# Sheet2.net
KiCad netlist of a schematic drawn in Altium Designer
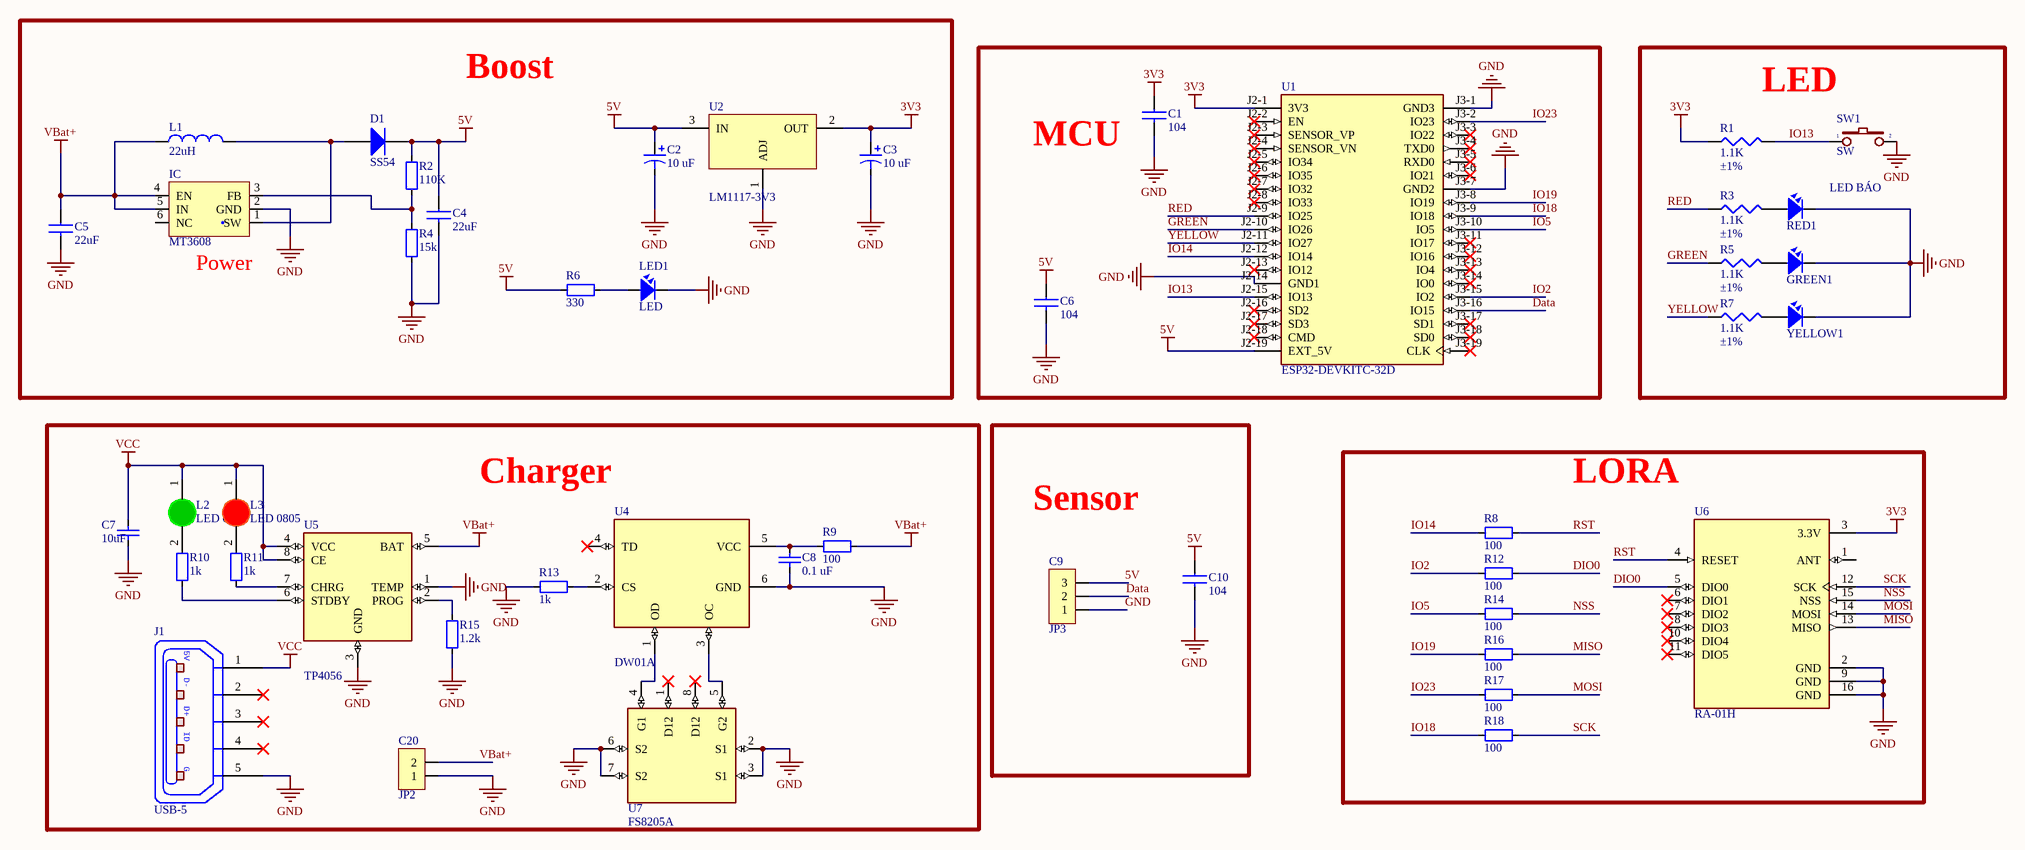
[diagram p0: Sheet2.SchDoc]

(export (version "E")
  (design (tool "Eeschema 10.0.6"))
  (components
    (comp (ref "C1")
      (value "104")
      (footprint "CAP0603")
      (description "CAP CER 30PF 50V NPO 0603")
      (fields
        (field (name "MANUFACTURER") "Yageo")
        (field (name "MANUFACTURER PART NUMBER") "CC0603JRNPO9BN300")
      )
      (libsource (lib "KhanhBK_SCH_Lib_6") (part "CC0603JRNPO9BN300"))
    )
    (comp (ref "C2")
      (value "10 uF")
      (footprint "C3MM")
      (description "Polarized Capacitor (Axial)")
      (fields (field (name "PUBLISHER") "Altium Limited"))
      (libsource (lib "My Library") (part "Cap Pol"))
    )
    (comp (ref "C3")
      (value "10 uF")
      (footprint "C3MM")
      (description "Polarized Capacitor (Axial)")
      (fields (field (name "PUBLISHER") "Altium Limited"))
      (libsource (lib "My Library") (part "Cap Pol"))
    )
    (comp (ref "C4")
      (value "22uF")
      (footprint "CAP0603")
      (description "CAP CER 30PF 50V NPO 0603")
      (fields
        (field (name "MANUFACTURER") "Yageo")
        (field (name "MANUFACTURER PART NUMBER") "CC0603JRNPO9BN300")
      )
      (libsource (lib "KhanhBK_SCH_Lib_6") (part "CC0603JRNPO9BN300"))
    )
    (comp (ref "C5")
      (value "22uF")
      (footprint "CAP0603")
      (description "CAP CER 30PF 50V NPO 0603")
      (fields
        (field (name "MANUFACTURER") "Yageo")
        (field (name "MANUFACTURER PART NUMBER") "CC0603JRNPO9BN300")
      )
      (libsource (lib "KhanhBK_SCH_Lib_6") (part "CC0603JRNPO9BN300"))
    )
    (comp (ref "C6")
      (value "104")
      (footprint "CAP0603")
      (description "CAP CER 30PF 50V NPO 0603")
      (fields
        (field (name "MANUFACTURER") "Yageo")
        (field (name "MANUFACTURER PART NUMBER") "CC0603JRNPO9BN300")
      )
      (libsource (lib "KhanhBK_SCH_Lib_6") (part "CC0603JRNPO9BN300"))
    )
    (comp (ref "C7")
      (value "10uF")
      (footprint "CAP_0805")
      (description "Capacitor")
      (fields (field (name "PUBLISHER") "Altium Limited"))
      (libsource (lib "My Library") (part "CapSMD"))
    )
    (comp (ref "C8")
      (value "0.1 uF")
      (footprint "CAP_0805")
      (description "Capacitor")
      (fields (field (name "PUBLISHER") "Altium Limited"))
      (libsource (lib "My Library") (part "CapSMD"))
    )
    (comp (ref "C9")
      (value "JP3")
      (footprint "JP3-C1T")
      (description "WR-PHD 2.54 mm Angled Socket Header")
      (fields
        (field (name "MANUFACTURER") "Würth Elektronik eiSos GmbH")
        (field (name "PARTNO") "613003143121")
        (field (name "CREATED BY") "Karrer Zheng")
      )
      (libsource (lib "KhanhBK_SCH_Library_1") (part "JP3"))
    )
    (comp (ref "C10")
      (value "104")
      (footprint "CAP0603")
      (description "CAP CER 30PF 50V NPO 0603")
      (fields
        (field (name "MANUFACTURER") "Yageo")
        (field (name "MANUFACTURER PART NUMBER") "CC0603JRNPO9BN300")
      )
      (libsource (lib "KhanhBK_SCH_Lib_6") (part "CC0603JRNPO9BN300"))
    )
    (comp (ref "C20")
      (value "JP2")
      (footprint "JP2-C1T")
      (description "WR-PHD 2.54 mm Angled Socket Header")
      (fields
        (field (name "MANUFACTURER") "Würth Elektronik eiSos GmbH")
        (field (name "PARTNO") "613002143121")
        (field (name "CREATED BY") "Karrer Zheng")
      )
      (libsource (lib "KhanhBK_SCH_Library_1") (part "JP2"))
    )
    (comp (ref "D1")
      (value "SS54")
      (footprint "DIODE/POW/1A")
      (description "Diode Power")
      (fields (field (name "PUBLISHER") "Altium Limited"))
      (libsource (lib "Cty1") (part "Diode Power"))
    )
    (comp (ref "GREEN1")
      (value "LED")
      (footprint "LED-3MM-GREEN")
      (description "LED Single colour Green and Red")
      (libsource (lib "KhanhBK_SCH_Library_1") (part "LED"))
    )
    (comp (ref "IC") (value "MT3608") (footprint "TSOP 2") (libsource (lib "MT3608") (part "MT3608")))
    (comp (ref "J1")
      (value "USB-5")
      (footprint "USB-M1")
      (fields
        (field (name "MANUFACTURER") "FCI")
        (field (name "MANUFACTURER PART NUMBER") "10118193-0001LF")
        (field (name ".CREATOR") "MM")
        (field (name ".CHECKED PCB") "RF")
        (field (name ".CHECKED SCH") "MM")
      )
      (libsource (lib "My Library") (part "USB-5"))
    )
    (comp (ref "L1")
      (value "22uH")
      (footprint "IND_400_500_212x114_SMD")
      (description "1mH Shielded Wirewound Inductor 600mA 1.82Ohm Max Nonstandard")
      (fields (field (name "MANUFACTURER") "Coilcraft") (field (name "MANUFACTURER PART NUMBER") "74477030"))
      (libsource (lib "Altium_Lib_by_KhueNguyenCreator") (part "IND_1mH-0.6A-20%-SMD"))
    )
    (comp (ref "L2")
      (value "LED 0805")
      (footprint "LED-0805-Green")
      (description "Dán")
      (libsource (lib "Altium_Lib_by_KhueNguyenCreator") (part "LED 0805 Xanh La"))
    )
    (comp (ref "L3")
      (value "LED 0805")
      (footprint "LED-0805-Red")
      (description "Dán")
      (libsource (lib "Altium_Lib_by_KhueNguyenCreator") (part "LED 0805 Do"))
    )
    (comp (ref "LED1")
      (value "LED")
      (footprint "LED-0805-Red")
      (description "LED Single colour Green and Red")
      (libsource (lib "My Library") (part "LED"))
    )
    (comp (ref "R1")
      (value "1.1K")
      (footprint "RES0603")
      (description "RES SMD 1K OHM 1% 1/10W 0603")
      (fields
        (field (name "MANUFACTURER") "Yageo")
        (field (name "MANUFACTURER PART NUMBER") "RT0603FRD071KL")
        (field (name "TOLERANCE") "±1%")
      )
      (libsource (lib "KhanhBK_SCH_Lib_6") (part "RT0603FRD071KL"))
    )
    (comp (ref "R2")
      (value "110K")
      (footprint "RES-SMD-0805")
      (description "Resistor")
      (fields
        (field (name "MANUFACTURER") "Generic Components")
        (field (name "PUBLISHER") "Altium Hobart Technology Centre")
      )
      (libsource (lib "My Library") (part "Resistor - SMD"))
    )
    (comp (ref "R3")
      (value "1.1K")
      (footprint "RES0603")
      (description "RES SMD 1K OHM 1% 1/10W 0603")
      (fields
        (field (name "MANUFACTURER") "Yageo")
        (field (name "MANUFACTURER PART NUMBER") "RT0603FRD071KL")
        (field (name "TOLERANCE") "±1%")
      )
      (libsource (lib "KhanhBK_SCH_Lib_6") (part "RT0603FRD071KL"))
    )
    (comp (ref "R4")
      (value "15k")
      (footprint "RES-SMD-0805")
      (description "Resistor")
      (fields
        (field (name "MANUFACTURER") "Generic Components")
        (field (name "PUBLISHER") "Altium Hobart Technology Centre")
      )
      (libsource (lib "My Library") (part "Resistor - SMD"))
    )
    (comp (ref "R5")
      (value "1.1K")
      (footprint "RES0603")
      (description "RES SMD 1K OHM 1% 1/10W 0603")
      (fields
        (field (name "MANUFACTURER") "Yageo")
        (field (name "MANUFACTURER PART NUMBER") "RT0603FRD071KL")
        (field (name "TOLERANCE") "±1%")
      )
      (libsource (lib "KhanhBK_SCH_Lib_6") (part "RT0603FRD071KL"))
    )
    (comp (ref "R6")
      (value "330")
      (footprint "RES-SMD-0805")
      (description "Resistor")
      (fields
        (field (name "MANUFACTURER") "Generic Components")
        (field (name "PUBLISHER") "Altium Hobart Technology Centre")
      )
      (libsource (lib "My Library") (part "Resistor - SMD"))
    )
    (comp (ref "R7")
      (value "1.1K")
      (footprint "RES0603")
      (description "RES SMD 1K OHM 1% 1/10W 0603")
      (fields
        (field (name "MANUFACTURER") "Yageo")
        (field (name "MANUFACTURER PART NUMBER") "RT0603FRD071KL")
        (field (name "TOLERANCE") "±1%")
      )
      (libsource (lib "KhanhBK_SCH_Lib_6") (part "RT0603FRD071KL"))
    )
    (comp (ref "R8")
      (value "100")
      (footprint "RES-SMD-0805")
      (description "Resistor")
      (fields
        (field (name "MANUFACTURER") "Generic Components")
        (field (name "PUBLISHER") "Altium Hobart Technology Centre")
      )
      (libsource (lib "My Library") (part "Resistor - SMD"))
    )
    (comp (ref "R9")
      (value "100")
      (footprint "RES-SMD-0805")
      (description "Resistor")
      (fields
        (field (name "MANUFACTURER") "Generic Components")
        (field (name "PUBLISHER") "Altium Hobart Technology Centre")
      )
      (libsource (lib "My Library") (part "Resistor - SMD"))
    )
    (comp (ref "R10")
      (value "1k")
      (footprint "RES-SMD-0805")
      (description "Resistor")
      (fields
        (field (name "MANUFACTURER") "Generic Components")
        (field (name "PUBLISHER") "Altium Hobart Technology Centre")
      )
      (libsource (lib "My Library") (part "Resistor - SMD"))
    )
    (comp (ref "R11")
      (value "1k")
      (footprint "RES-SMD-0805")
      (description "Resistor")
      (fields
        (field (name "MANUFACTURER") "Generic Components")
        (field (name "PUBLISHER") "Altium Hobart Technology Centre")
      )
      (libsource (lib "My Library") (part "Resistor - SMD"))
    )
    (comp (ref "R12")
      (value "100")
      (footprint "RES-SMD-0805")
      (description "Resistor")
      (fields
        (field (name "MANUFACTURER") "Generic Components")
        (field (name "PUBLISHER") "Altium Hobart Technology Centre")
      )
      (libsource (lib "My Library") (part "Resistor - SMD"))
    )
    (comp (ref "R13")
      (value "1k")
      (footprint "RES-SMD-0805")
      (description "Resistor")
      (fields
        (field (name "MANUFACTURER") "Generic Components")
        (field (name "PUBLISHER") "Altium Hobart Technology Centre")
      )
      (libsource (lib "My Library") (part "Resistor - SMD"))
    )
    (comp (ref "R14")
      (value "100")
      (footprint "RES-SMD-0805")
      (description "Resistor")
      (fields
        (field (name "MANUFACTURER") "Generic Components")
        (field (name "PUBLISHER") "Altium Hobart Technology Centre")
      )
      (libsource (lib "My Library") (part "Resistor - SMD"))
    )
    (comp (ref "R15")
      (value "1.2k")
      (footprint "RES-SMD-0805")
      (description "Resistor")
      (fields
        (field (name "MANUFACTURER") "Generic Components")
        (field (name "PUBLISHER") "Altium Hobart Technology Centre")
      )
      (libsource (lib "My Library") (part "Resistor - SMD"))
    )
    (comp (ref "R16")
      (value "100")
      (footprint "RES-SMD-0805")
      (description "Resistor")
      (fields
        (field (name "MANUFACTURER") "Generic Components")
        (field (name "PUBLISHER") "Altium Hobart Technology Centre")
      )
      (libsource (lib "My Library") (part "Resistor - SMD"))
    )
    (comp (ref "R17")
      (value "100")
      (footprint "RES-SMD-0805")
      (description "Resistor")
      (fields
        (field (name "MANUFACTURER") "Generic Components")
        (field (name "PUBLISHER") "Altium Hobart Technology Centre")
      )
      (libsource (lib "My Library") (part "Resistor - SMD"))
    )
    (comp (ref "R18")
      (value "100")
      (footprint "RES-SMD-0805")
      (description "Resistor")
      (fields
        (field (name "MANUFACTURER") "Generic Components")
        (field (name "PUBLISHER") "Altium Hobart Technology Centre")
      )
      (libsource (lib "My Library") (part "Resistor - SMD"))
    )
    (comp (ref "RED1")
      (value "LED")
      (footprint "LED-3MM-RED")
      (description "LED Single colour Green and Red")
      (libsource (lib "KhanhBK_SCH_Library_1") (part "LED"))
    )
    (comp (ref "SW1")
      (value "SW")
      (footprint "SW1-SMD")
      (description "Switch button 2 pin")
      (libsource (lib "KhanhBK_SCH_Library_1") (part "SW2"))
    )
    (comp (ref "U1")
      (value "ESP32-DEVKITC-32D")
      (footprint "MODULE_ESP32-DEVKITC-32D")
      (description "WiFi Development Tools (802.11) ESP32 General Development Kit, ESP32-WROOM-32D on the board")
      (fields (field (name "MF") "Espressif Systems"))
      (libsource (lib "ESP32-DEVKITC-32D") (part "ESP32-DEVKITC-32D"))
    )
    (comp (ref "U2")
      (value "LM1117-3V3")
      (footprint "LM1117-SOP")
      (description "800mA Low-Dropout Linear Regulator")
      (fields (field (name "CREATOR") "Nguyen Ba Bien"))
      (libsource (lib "My Library") (part "LM1117-ADJ"))
    )
    (comp (ref "U4")
      (value "DW01A")
      (footprint "SOT23-6")
      (description "One Cell Lithium-ion/Polymer Battery Protection IC")
      (libsource (lib "My Library") (part "DW01A"))
    )
    (comp (ref "U5")
      (value "TP4056")
      (footprint "TP4056")
      (description "Complete single cell Li-Ion battery with a constant current / constant voltage linear charger")
      (libsource (lib "My Library") (part "TP4056"))
    )
    (comp (ref "U6")
      (value "RA-01H")
      (footprint "XCVR_RA-01H")
      (fields (field (name "MF") "AI-Thinker"))
      (libsource (lib "RA-01H") (part "RA-01H"))
    )
    (comp (ref "U7") (value "FS8205A") (footprint "FS8205A") (libsource (lib "My Library") (part "FS8205A")))
    (comp (ref "YELLOW1")
      (value "LED")
      (footprint "LED-3MM-YELLOW")
      (description "LED Single colour Green and Red")
      (libsource (lib "KhanhBK_SCH_Library_1") (part "LED"))
    )
  )
  (nets
    (net (code "1") (name "/DIO0") (class "Default")
      (node (ref "R12") (pin "2") (pinfunction "2_2") (pintype "passive"))
      (node (ref "U6") (pin "5") (pinfunction "DIO0_5") (pintype "bidirectional"))
    )
    (net (code "2") (name "/Data") (class "Default")
      (node (ref "C9") (pin "2") (pinfunction "2_2") (pintype "passive"))
      (node (ref "U1") (pin "J3-16") (pinfunction "IO15_J3-16") (pintype "bidirectional"))
    )
    (net (code "3") (name "/GREEN") (class "Default")
      (node (ref "R5") (pin "1") (pinfunction "1_1") (pintype "passive"))
      (node (ref "U1") (pin "J2-10") (pinfunction "IO26_J2-10") (pintype "bidirectional"))
    )
    (net (code "4") (name "/IO2") (class "Default")
      (node (ref "R12") (pin "1") (pinfunction "1_1") (pintype "passive"))
      (node (ref "U1") (pin "J3-15") (pinfunction "IO2_J3-15") (pintype "bidirectional"))
    )
    (net (code "5") (name "/IO5") (class "Default")
      (node (ref "R14") (pin "1") (pinfunction "1_1") (pintype "passive"))
      (node (ref "U1") (pin "J3-10") (pinfunction "IO5_J3-10") (pintype "bidirectional"))
    )
    (net (code "6") (name "/IO13") (class "Default")
      (node (ref "R1") (pin "2") (pinfunction "2_2") (pintype "passive"))
      (node (ref "SW1") (pin "1") (pinfunction "1_1") (pintype "passive"))
      (node (ref "U1") (pin "J2-15") (pinfunction "IO13_J2-15") (pintype "bidirectional"))
    )
    (net (code "7") (name "/IO14") (class "Default")
      (node (ref "R8") (pin "1") (pinfunction "1_1") (pintype "passive"))
      (node (ref "U1") (pin "J2-12") (pinfunction "IO14_J2-12") (pintype "bidirectional"))
    )
    (net (code "8") (name "/IO18") (class "Default")
      (node (ref "R18") (pin "1") (pinfunction "1_1") (pintype "passive"))
      (node (ref "U1") (pin "J3-9") (pinfunction "IO18_J3-9") (pintype "bidirectional"))
    )
    (net (code "9") (name "/IO19") (class "Default")
      (node (ref "R16") (pin "1") (pinfunction "1_1") (pintype "passive"))
      (node (ref "U1") (pin "J3-8") (pinfunction "IO19_J3-8") (pintype "bidirectional"))
    )
    (net (code "10") (name "/IO23") (class "Default")
      (node (ref "R17") (pin "1") (pinfunction "1_1") (pintype "passive"))
      (node (ref "U1") (pin "J3-2") (pinfunction "IO23_J3-2") (pintype "bidirectional"))
    )
    (net (code "11") (name "/MISO") (class "Default")
      (node (ref "R16") (pin "2") (pinfunction "2_2") (pintype "passive"))
      (node (ref "U6") (pin "13") (pinfunction "MISO_13") (pintype "output"))
    )
    (net (code "12") (name "/MOSI") (class "Default")
      (node (ref "R17") (pin "2") (pinfunction "2_2") (pintype "passive"))
      (node (ref "U6") (pin "14") (pinfunction "MOSI_14") (pintype "input"))
    )
    (net (code "13") (name "/NSS") (class "Default")
      (node (ref "R14") (pin "2") (pinfunction "2_2") (pintype "passive"))
      (node (ref "U6") (pin "15") (pinfunction "NSS_15") (pintype "input"))
    )
    (net (code "14") (name "/RED") (class "Default")
      (node (ref "R3") (pin "1") (pinfunction "1_1") (pintype "passive"))
      (node (ref "U1") (pin "J2-9") (pinfunction "IO25_J2-9") (pintype "bidirectional"))
    )
    (net (code "15") (name "/RST") (class "Default")
      (node (ref "R8") (pin "2") (pinfunction "2_2") (pintype "passive"))
      (node (ref "U6") (pin "4") (pinfunction "RESET_4") (pintype "input"))
    )
    (net (code "16") (name "/SCK") (class "Default")
      (node (ref "R18") (pin "2") (pinfunction "2_2") (pintype "passive"))
      (node (ref "U6") (pin "12") (pinfunction "SCK_12") (pintype "input"))
    )
    (net (code "17") (name "/YELLOW") (class "Default")
      (node (ref "R7") (pin "1") (pinfunction "1_1") (pintype "passive"))
      (node (ref "U1") (pin "J2-11") (pinfunction "IO27_J2-11") (pintype "bidirectional"))
    )
    (net (code "18") (name "3V3") (class "Default")
      (node (ref "C1") (pin "1") (pinfunction "1_1") (pintype "passive"))
      (node (ref "C3") (pin "1") (pinfunction "1_1") (pintype "passive"))
      (node (ref "R1") (pin "1") (pinfunction "1_1") (pintype "passive"))
      (node (ref "U1") (pin "J2-1") (pinfunction "3V3_J2-1") (pintype "power_in"))
      (node (ref "U2") (pin "2") (pinfunction "OUT_2") (pintype "passive"))
      (node (ref "U6") (pin "3") (pinfunction "3.3V_3") (pintype "power_in"))
    )
    (net (code "19") (name "5V") (class "Default")
      (node (ref "C10") (pin "1") (pinfunction "1_1") (pintype "passive"))
      (node (ref "C2") (pin "1") (pinfunction "1_1") (pintype "passive"))
      (node (ref "C4") (pin "1") (pinfunction "1_1") (pintype "passive"))
      (node (ref "C6") (pin "1") (pinfunction "1_1") (pintype "passive"))
      (node (ref "C9") (pin "3") (pinfunction "3_3") (pintype "passive"))
      (node (ref "D1") (pin "2") (pinfunction "K_2") (pintype "passive"))
      (node (ref "R2") (pin "2") (pinfunction "2_2") (pintype "passive"))
      (node (ref "R6") (pin "1") (pinfunction "1_1") (pintype "passive"))
      (node (ref "U1") (pin "J2-19") (pinfunction "EXT_5V_J2-19") (pintype "power_in"))
      (node (ref "U2") (pin "3") (pinfunction "IN_3") (pintype "passive"))
    )
    (net (code "20") (name "GND") (class "Default")
      (node (ref "C1") (pin "2") (pinfunction "2_2") (pintype "passive"))
      (node (ref "C10") (pin "2") (pinfunction "2_2") (pintype "passive"))
      (node (ref "C2") (pin "2") (pinfunction "2_2") (pintype "passive"))
      (node (ref "C20") (pin "1") (pinfunction "1_1") (pintype "passive"))
      (node (ref "C3") (pin "2") (pinfunction "2_2") (pintype "passive"))
      (node (ref "C4") (pin "2") (pinfunction "2_2") (pintype "passive"))
      (node (ref "C5") (pin "2") (pinfunction "2_2") (pintype "passive"))
      (node (ref "C6") (pin "2") (pinfunction "2_2") (pintype "passive"))
      (node (ref "C7") (pin "1") (pinfunction "1_1") (pintype "passive"))
      (node (ref "C8") (pin "1") (pinfunction "1_1") (pintype "passive"))
      (node (ref "C9") (pin "1") (pinfunction "1_1") (pintype "passive"))
      (node (ref "GREEN1") (pin "2") (pinfunction "2_2") (pintype "passive"))
      (node (ref "IC") (pin "2") (pinfunction "GND_2") (pintype "power_in"))
      (node (ref "J1") (pin "5") (pinfunction "P5_5") (pintype "passive"))
      (node (ref "LED1") (pin "2") (pinfunction "2_2") (pintype "passive"))
      (node (ref "R13") (pin "1") (pinfunction "1_1") (pintype "passive"))
      (node (ref "R15") (pin "1") (pinfunction "1_1") (pintype "passive"))
      (node (ref "R4") (pin "1") (pinfunction "1_1") (pintype "passive"))
      (node (ref "RED1") (pin "2") (pinfunction "2_2") (pintype "passive"))
      (node (ref "SW1") (pin "2") (pinfunction "2_2") (pintype "passive"))
      (node (ref "U1") (pin "J2-14") (pinfunction "GND1_J2-14") (pintype "power_in"))
      (node (ref "U1") (pin "J3-1") (pinfunction "GND3_J3-1") (pintype "power_in"))
      (node (ref "U1") (pin "J3-7") (pinfunction "GND2_J3-7") (pintype "power_in"))
      (node (ref "U2") (pin "1") (pinfunction "ADJ_1") (pintype "passive"))
      (node (ref "U4") (pin "6") (pinfunction "GND_6") (pintype "power_in"))
      (node (ref "U5") (pin "1") (pinfunction "TEMP_1") (pintype "bidirectional"))
      (node (ref "U5") (pin "3") (pinfunction "GND_3") (pintype "bidirectional"))
      (node (ref "U6") (pin "16") (pinfunction "GND_16") (pintype "power_in"))
      (node (ref "U6") (pin "2") (pinfunction "GND_2") (pintype "power_in"))
      (node (ref "U6") (pin "9") (pinfunction "GND_9") (pintype "power_in"))
      (node (ref "U7") (pin "2") (pinfunction "S1_2") (pintype "bidirectional"))
      (node (ref "U7") (pin "3") (pinfunction "S1_3") (pintype "bidirectional"))
      (node (ref "U7") (pin "6") (pinfunction "S2_6") (pintype "bidirectional"))
      (node (ref "U7") (pin "7") (pinfunction "S2_7") (pintype "bidirectional"))
      (node (ref "YELLOW1") (pin "2") (pinfunction "2_2") (pintype "passive"))
    )
    (net (code "21") (name "Net-(D1-A)") (class "Default")
      (node (ref "D1") (pin "1") (pinfunction "A_1") (pintype "passive"))
      (node (ref "IC") (pin "1") (pinfunction "SW_1") (pintype "power_in"))
      (node (ref "L1") (pin "2") (pinfunction "2_2") (pintype "passive"))
    )
    (net (code "22") (name "Net-(GREEN1-Pad1)") (class "Default")
      (node (ref "GREEN1") (pin "1") (pinfunction "1_1") (pintype "passive"))
      (node (ref "R5") (pin "2") (pinfunction "2_2") (pintype "passive"))
    )
    (net (code "23") (name "Net-(IC-FB)") (class "Default")
      (node (ref "IC") (pin "3") (pinfunction "FB_3") (pintype "power_in"))
      (node (ref "R2") (pin "1") (pinfunction "1_1") (pintype "passive"))
      (node (ref "R4") (pin "2") (pinfunction "2_2") (pintype "passive"))
    )
    (net (code "24") (name "Net-(L2-K)") (class "Default")
      (node (ref "L2") (pin "2") (pinfunction "K_2") (pintype "passive"))
      (node (ref "R10") (pin "2") (pinfunction "2_2") (pintype "passive"))
    )
    (net (code "25") (name "Net-(L3-K)") (class "Default")
      (node (ref "L3") (pin "2") (pinfunction "K_2") (pintype "passive"))
      (node (ref "R11") (pin "2") (pinfunction "2_2") (pintype "passive"))
    )
    (net (code "26") (name "Net-(LED1-Pad1)") (class "Default")
      (node (ref "LED1") (pin "1") (pinfunction "1_1") (pintype "passive"))
      (node (ref "R6") (pin "2") (pinfunction "2_2") (pintype "passive"))
    )
    (net (code "27") (name "Net-(R3-Pad2)") (class "Default")
      (node (ref "R3") (pin "2") (pinfunction "2_2") (pintype "passive"))
      (node (ref "RED1") (pin "1") (pinfunction "1_1") (pintype "passive"))
    )
    (net (code "28") (name "Net-(R7-Pad2)") (class "Default")
      (node (ref "R7") (pin "2") (pinfunction "2_2") (pintype "passive"))
      (node (ref "YELLOW1") (pin "1") (pinfunction "1_1") (pintype "passive"))
    )
    (net (code "29") (name "Net-(U4-CS)") (class "Default")
      (node (ref "R13") (pin "2") (pinfunction "2_2") (pintype "passive"))
      (node (ref "U4") (pin "2") (pinfunction "CS_2") (pintype "bidirectional"))
    )
    (net (code "30") (name "Net-(U4-OC)") (class "Default")
      (node (ref "U4") (pin "3") (pinfunction "OC_3") (pintype "bidirectional"))
      (node (ref "U7") (pin "5") (pinfunction "G2_5") (pintype "bidirectional"))
    )
    (net (code "31") (name "Net-(U4-OD)") (class "Default")
      (node (ref "U4") (pin "1") (pinfunction "OD_1") (pintype "bidirectional"))
      (node (ref "U7") (pin "4") (pinfunction "G1_4") (pintype "bidirectional"))
    )
    (net (code "32") (name "Net-(U4-VCC)") (class "Default")
      (node (ref "C8") (pin "2") (pinfunction "2_2") (pintype "passive"))
      (node (ref "R9") (pin "1") (pinfunction "1_1") (pintype "passive"))
      (node (ref "U4") (pin "5") (pinfunction "VCC_5") (pintype "power_in"))
    )
    (net (code "33") (name "Net-(U5-CHRG)") (class "Default")
      (node (ref "R11") (pin "1") (pinfunction "1_1") (pintype "passive"))
      (node (ref "U5") (pin "7") (pinfunction "CHRG_7") (pintype "bidirectional"))
    )
    (net (code "34") (name "Net-(U5-PROG)") (class "Default")
      (node (ref "R15") (pin "2") (pinfunction "2_2") (pintype "passive"))
      (node (ref "U5") (pin "2") (pinfunction "PROG_2") (pintype "bidirectional"))
    )
    (net (code "35") (name "Net-(U5-STDBY)") (class "Default")
      (node (ref "R10") (pin "1") (pinfunction "1_1") (pintype "passive"))
      (node (ref "U5") (pin "6") (pinfunction "STDBY_6") (pintype "bidirectional"))
    )
    (net (code "36") (name "VBat+") (class "Default")
      (node (ref "C20") (pin "2") (pinfunction "2_2") (pintype "passive"))
      (node (ref "C5") (pin "1") (pinfunction "1_1") (pintype "passive"))
      (node (ref "IC") (pin "4") (pinfunction "EN_4") (pintype "power_in"))
      (node (ref "IC") (pin "5") (pinfunction "IN_5") (pintype "power_in"))
      (node (ref "L1") (pin "1") (pinfunction "1_1") (pintype "passive"))
      (node (ref "R9") (pin "2") (pinfunction "2_2") (pintype "passive"))
      (node (ref "U5") (pin "5") (pinfunction "BAT_5") (pintype "bidirectional"))
    )
    (net (code "37") (name "VCC") (class "Default")
      (node (ref "C7") (pin "2") (pinfunction "2_2") (pintype "passive"))
      (node (ref "J1") (pin "1") (pinfunction "P1_1") (pintype "passive"))
      (node (ref "L2") (pin "1") (pinfunction "A_1") (pintype "passive"))
      (node (ref "L3") (pin "1") (pinfunction "A_1") (pintype "passive"))
      (node (ref "U5") (pin "4") (pinfunction "VCC_4") (pintype "bidirectional"))
      (node (ref "U5") (pin "8") (pinfunction "CE_8") (pintype "bidirectional"))
    )
    (net (code "38") (name "unconnected-(IC-NC-Pad6)") (class "Default")
      (node (ref "IC") (pin "6") (pinfunction "NC_6") (pintype "power_in"))
    )
    (net (code "39") (name "unconnected-(J1-P2-Pad2)") (class "Default")
      (node (ref "J1") (pin "2") (pinfunction "P2_2") (pintype "passive+no_connect"))
    )
    (net (code "40") (name "unconnected-(J1-P3-Pad3)") (class "Default")
      (node (ref "J1") (pin "3") (pinfunction "P3_3") (pintype "passive+no_connect"))
    )
    (net (code "41") (name "unconnected-(J1-P4-Pad4)") (class "Default")
      (node (ref "J1") (pin "4") (pinfunction "P4_4") (pintype "passive+no_connect"))
    )
    (net (code "42") (name "unconnected-(U1-CLK-PadJ3-19)") (class "Default")
      (node (ref "U1") (pin "J3-19") (pinfunction "CLK_J3-19") (pintype "input+no_connect"))
    )
    (net (code "43") (name "unconnected-(U1-CMD-PadJ2-18)") (class "Default")
      (node (ref "U1") (pin "J2-18") (pinfunction "CMD_J2-18") (pintype "bidirectional+no_connect"))
    )
    (net (code "44") (name "unconnected-(U1-EN-PadJ2-2)") (class "Default")
      (node (ref "U1") (pin "J2-2") (pinfunction "EN_J2-2") (pintype "input+no_connect"))
    )
    (net (code "45") (name "unconnected-(U1-IO0-PadJ3-14)") (class "Default")
      (node (ref "U1") (pin "J3-14") (pinfunction "IO0_J3-14") (pintype "bidirectional+no_connect"))
    )
    (net (code "46") (name "unconnected-(U1-IO4-PadJ3-13)") (class "Default")
      (node (ref "U1") (pin "J3-13") (pinfunction "IO4_J3-13") (pintype "bidirectional+no_connect"))
    )
    (net (code "47") (name "unconnected-(U1-IO12-PadJ2-13)") (class "Default")
      (node (ref "U1") (pin "J2-13") (pinfunction "IO12_J2-13") (pintype "bidirectional+no_connect"))
    )
    (net (code "48") (name "unconnected-(U1-IO16-PadJ3-12)") (class "Default")
      (node (ref "U1") (pin "J3-12") (pinfunction "IO16_J3-12") (pintype "bidirectional+no_connect"))
    )
    (net (code "49") (name "unconnected-(U1-IO17-PadJ3-11)") (class "Default")
      (node (ref "U1") (pin "J3-11") (pinfunction "IO17_J3-11") (pintype "bidirectional+no_connect"))
    )
    (net (code "50") (name "unconnected-(U1-IO21-PadJ3-6)") (class "Default")
      (node (ref "U1") (pin "J3-6") (pinfunction "IO21_J3-6") (pintype "bidirectional+no_connect"))
    )
    (net (code "51") (name "unconnected-(U1-IO22-PadJ3-3)") (class "Default")
      (node (ref "U1") (pin "J3-3") (pinfunction "IO22_J3-3") (pintype "bidirectional+no_connect"))
    )
    (net (code "52") (name "unconnected-(U1-IO32-PadJ2-7)") (class "Default")
      (node (ref "U1") (pin "J2-7") (pinfunction "IO32_J2-7") (pintype "bidirectional+no_connect"))
    )
    (net (code "53") (name "unconnected-(U1-IO33-PadJ2-8)") (class "Default")
      (node (ref "U1") (pin "J2-8") (pinfunction "IO33_J2-8") (pintype "bidirectional+no_connect"))
    )
    (net (code "54") (name "unconnected-(U1-IO34-PadJ2-5)") (class "Default")
      (node (ref "U1") (pin "J2-5") (pinfunction "IO34_J2-5") (pintype "bidirectional+no_connect"))
    )
    (net (code "55") (name "unconnected-(U1-IO35-PadJ2-6)") (class "Default")
      (node (ref "U1") (pin "J2-6") (pinfunction "IO35_J2-6") (pintype "bidirectional+no_connect"))
    )
    (net (code "56") (name "unconnected-(U1-RXD0-PadJ3-5)") (class "Default")
      (node (ref "U1") (pin "J3-5") (pinfunction "RXD0_J3-5") (pintype "input+no_connect"))
    )
    (net (code "57") (name "unconnected-(U1-SD0-PadJ3-18)") (class "Default")
      (node (ref "U1") (pin "J3-18") (pinfunction "SD0_J3-18") (pintype "bidirectional+no_connect"))
    )
    (net (code "58") (name "unconnected-(U1-SD1-PadJ3-17)") (class "Default")
      (node (ref "U1") (pin "J3-17") (pinfunction "SD1_J3-17") (pintype "bidirectional+no_connect"))
    )
    (net (code "59") (name "unconnected-(U1-SD2-PadJ2-16)") (class "Default")
      (node (ref "U1") (pin "J2-16") (pinfunction "SD2_J2-16") (pintype "bidirectional+no_connect"))
    )
    (net (code "60") (name "unconnected-(U1-SD3-PadJ2-17)") (class "Default")
      (node (ref "U1") (pin "J2-17") (pinfunction "SD3_J2-17") (pintype "bidirectional+no_connect"))
    )
    (net (code "61") (name "unconnected-(U1-SENSOR_VN-PadJ2-4)") (class "Default")
      (node (ref "U1") (pin "J2-4") (pinfunction "SENSOR_VN_J2-4") (pintype "input+no_connect"))
    )
    (net (code "62") (name "unconnected-(U1-SENSOR_VP-PadJ2-3)") (class "Default")
      (node (ref "U1") (pin "J2-3") (pinfunction "SENSOR_VP_J2-3") (pintype "input+no_connect"))
    )
    (net (code "63") (name "unconnected-(U1-TXD0-PadJ3-4)") (class "Default")
      (node (ref "U1") (pin "J3-4") (pinfunction "TXD0_J3-4") (pintype "output+no_connect"))
    )
    (net (code "64") (name "unconnected-(U4-TD-Pad4)") (class "Default")
      (node (ref "U4") (pin "4") (pinfunction "TD_4") (pintype "bidirectional+no_connect"))
    )
    (net (code "65") (name "unconnected-(U6-ANT-Pad1)") (class "Default")
      (node (ref "U6") (pin "1") (pinfunction "ANT_1") (pintype "bidirectional"))
    )
    (net (code "66") (name "unconnected-(U6-DIO1-Pad6)") (class "Default")
      (node (ref "U6") (pin "6") (pinfunction "DIO1_6") (pintype "bidirectional+no_connect"))
    )
    (net (code "67") (name "unconnected-(U6-DIO2-Pad7)") (class "Default")
      (node (ref "U6") (pin "7") (pinfunction "DIO2_7") (pintype "bidirectional+no_connect"))
    )
    (net (code "68") (name "unconnected-(U6-DIO3-Pad8)") (class "Default")
      (node (ref "U6") (pin "8") (pinfunction "DIO3_8") (pintype "bidirectional+no_connect"))
    )
    (net (code "69") (name "unconnected-(U6-DIO4-Pad10)") (class "Default")
      (node (ref "U6") (pin "10") (pinfunction "DIO4_10") (pintype "bidirectional+no_connect"))
    )
    (net (code "70") (name "unconnected-(U6-DIO5-Pad11)") (class "Default")
      (node (ref "U6") (pin "11") (pinfunction "DIO5_11") (pintype "bidirectional+no_connect"))
    )
    (net (code "71") (name "unconnected-(U7-D12-Pad1)") (class "Default")
      (node (ref "U7") (pin "1") (pinfunction "D12_1") (pintype "bidirectional+no_connect"))
    )
    (net (code "72") (name "unconnected-(U7-D12-Pad8)") (class "Default")
      (node (ref "U7") (pin "8") (pinfunction "D12_8") (pintype "bidirectional+no_connect"))
    )
  )
)
